# nivel_digital.net
KiCad netlist of a schematic drawn in EAGLE
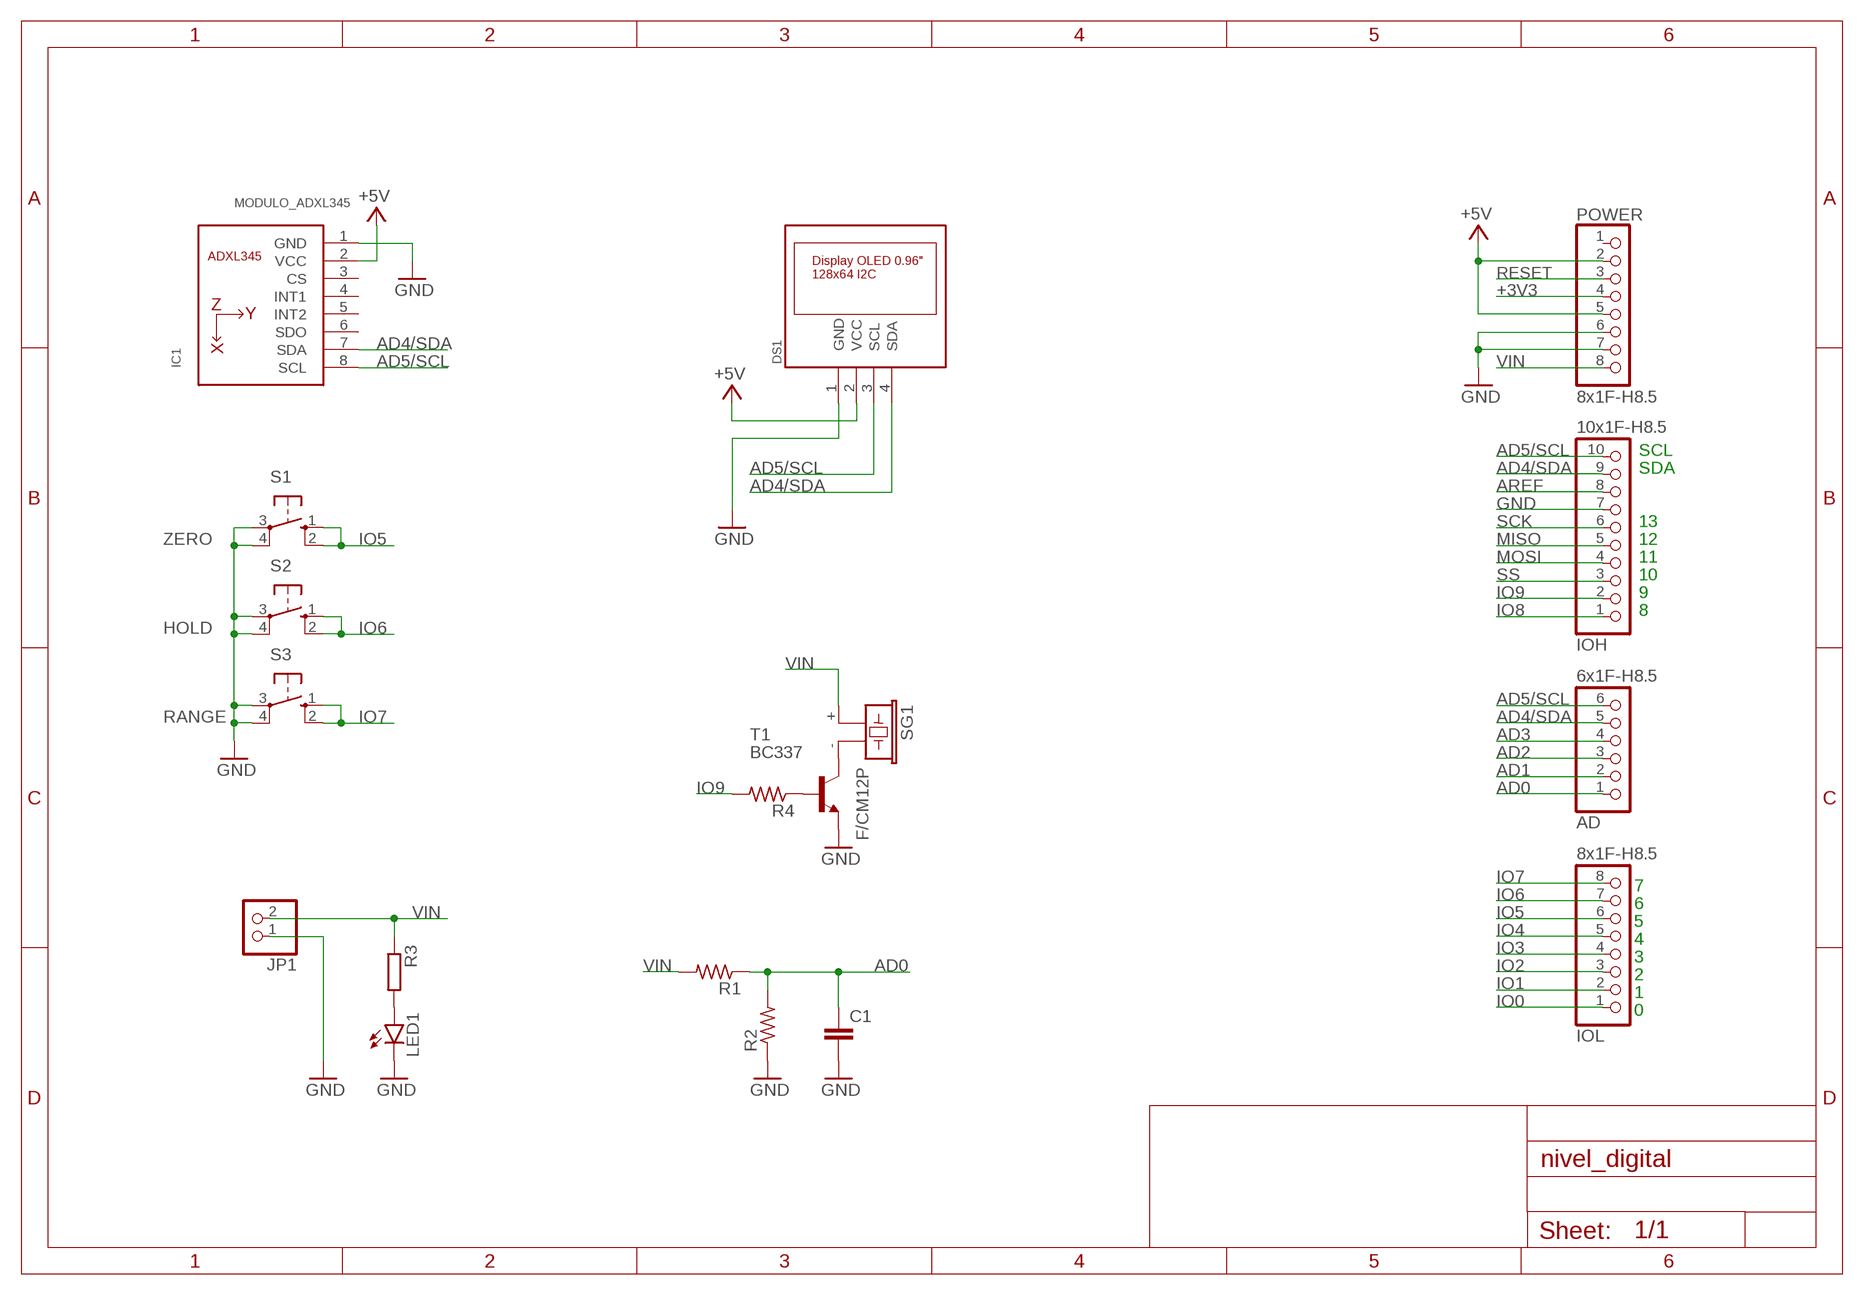
[diagram p0: schematic, sheet 1]

(export (version "E")
  (design (tool "Eeschema 10.0.6"))
  (components
    (comp (ref "AD")
      (value "6x1F-H8.5")
      (footprint "eagle-import:1X06")
      (libsource (lib "eagle-import") (part "PINHD-1X6"))
    )
    (comp (ref "C1")
      (value "C-EU050-025X075")
      (footprint "eagle-import:C050-025X075")
      (libsource (lib "eagle-import") (part "C-EU050-025X075"))
    )
    (comp (ref "DS1")
      (value "OLED_0.96_I2C")
      (footprint "eagle-import:OLED_0.96_I2C")
      (libsource (lib "eagle-import") (part "OLED_0.96_I2C"))
    )
    (comp (ref "IC1")
      (value "MODULO_ADXL345")
      (footprint "eagle-import:MODULO_ADXL345")
      (libsource (lib "eagle-import") (part "MODULO_ADXL345"))
    )
    (comp (ref "IOH")
      (value "10x1F-H8.5")
      (footprint "eagle-import:1X10")
      (libsource (lib "eagle-import") (part "PINHD-1X10_ARD"))
    )
    (comp (ref "IOL")
      (value "8x1F-H8.5")
      (footprint "eagle-import:1X08")
      (libsource (lib "eagle-import") (part "PINHD-1X8"))
    )
    (comp (ref "JP1")
      (value "PINHD-1X2/90")
      (footprint "eagle-import:1X02_90")
      (libsource (lib "eagle-import") (part "PINHD-1X2/90"))
    )
    (comp (ref "LED1")
      (value "LED5MM")
      (footprint "eagle-import:LED5MM")
      (libsource (lib "eagle-import") (part "LED5MM"))
    )
    (comp (ref "POWER")
      (value "8x1F-H8.5")
      (footprint "eagle-import:1X08")
      (libsource (lib "eagle-import") (part "PINHD-1X8"))
    )
    (comp (ref "R1")
      (value "R-US_0204/7")
      (footprint "eagle-import:0204_7")
      (libsource (lib "eagle-import") (part "R-US_0204/7"))
    )
    (comp (ref "R2")
      (value "R-US_0204/7")
      (footprint "eagle-import:0204_7")
      (libsource (lib "eagle-import") (part "R-US_0204/7"))
    )
    (comp (ref "R3")
      (value "R-EU_0207/10")
      (footprint "eagle-import:0207_10")
      (libsource (lib "eagle-import") (part "R-EU_0207/10"))
    )
    (comp (ref "R4")
      (value "R-US_0204/7")
      (footprint "eagle-import:0204_7")
      (libsource (lib "eagle-import") (part "R-US_0204/7"))
    )
    (comp (ref "S1")
      (value "10-XXPUSH-BUTTON-5MM")
      (footprint "eagle-import:B3F-10XX")
      (libsource (lib "eagle-import") (part "10-XXPUSH-BUTTON-5MM"))
    )
    (comp (ref "S2")
      (value "10-XXPUSH-BUTTON-5MM")
      (footprint "eagle-import:B3F-10XX")
      (libsource (lib "eagle-import") (part "10-XXPUSH-BUTTON-5MM"))
    )
    (comp (ref "S3")
      (value "10-XXPUSH-BUTTON-5MM")
      (footprint "eagle-import:B3F-10XX")
      (libsource (lib "eagle-import") (part "10-XXPUSH-BUTTON-5MM"))
    )
    (comp (ref "SG1")
      (value "F/CM12P")
      (footprint "eagle-import:F_CM12P")
      (libsource (lib "eagle-import") (part "F/CM12P"))
    )
    (comp (ref "T1")
      (value "BC337")
      (footprint "eagle-import:TO92")
      (libsource (lib "eagle-import") (part "BC337"))
    )
  )
  (nets
    (net (code "1") (name "+5V") (class "Default")
      (node (ref "DS1") (pin "2") (pinfunction "VCC_2") (pintype "power_in"))
      (node (ref "IC1") (pin "2") (pinfunction "VCC_2") (pintype "power_in"))
      (node (ref "POWER") (pin "2") (pinfunction "2_2") (pintype "passive"))
      (node (ref "POWER") (pin "5") (pinfunction "5_5") (pintype "passive"))
    )
    (net (code "2") (name "/+3V3") (class "Default")
      (node (ref "POWER") (pin "4") (pinfunction "4_4") (pintype "passive"))
    )
    (net (code "3") (name "/AD0") (class "Default")
      (node (ref "AD") (pin "1") (pinfunction "1_1") (pintype "passive"))
      (node (ref "C1") (pin "1") (pinfunction "1_1") (pintype "passive"))
      (node (ref "R1") (pin "1") (pinfunction "1_1") (pintype "passive"))
      (node (ref "R2") (pin "2") (pinfunction "2_2") (pintype "passive"))
    )
    (net (code "4") (name "/AD1") (class "Default")
      (node (ref "AD") (pin "2") (pinfunction "2_2") (pintype "passive"))
    )
    (net (code "5") (name "/AD2") (class "Default")
      (node (ref "AD") (pin "3") (pinfunction "3_3") (pintype "passive"))
    )
    (net (code "6") (name "/AD3") (class "Default")
      (node (ref "AD") (pin "4") (pinfunction "4_4") (pintype "passive"))
    )
    (net (code "7") (name "/AD4{slash}SDA") (class "Default")
      (node (ref "AD") (pin "5") (pinfunction "5_5") (pintype "passive"))
      (node (ref "DS1") (pin "4") (pinfunction "SDA_4") (pintype "bidirectional"))
      (node (ref "IC1") (pin "7") (pinfunction "SDA_7") (pintype "bidirectional"))
      (node (ref "IOH") (pin "9") (pinfunction "9_9") (pintype "passive"))
    )
    (net (code "8") (name "/AD5{slash}SCL") (class "Default")
      (node (ref "AD") (pin "6") (pinfunction "6_6") (pintype "passive"))
      (node (ref "DS1") (pin "3") (pinfunction "SCL_3") (pintype "bidirectional"))
      (node (ref "IC1") (pin "8") (pinfunction "SCL_8") (pintype "input"))
      (node (ref "IOH") (pin "10") (pinfunction "10_10") (pintype "passive"))
    )
    (net (code "9") (name "/AREF") (class "Default")
      (node (ref "IOH") (pin "8") (pinfunction "8_8") (pintype "passive"))
    )
    (net (code "10") (name "/IO0") (class "Default")
      (node (ref "IOL") (pin "1") (pinfunction "1_1") (pintype "passive"))
    )
    (net (code "11") (name "/IO1") (class "Default")
      (node (ref "IOL") (pin "2") (pinfunction "2_2") (pintype "passive"))
    )
    (net (code "12") (name "/IO2") (class "Default")
      (node (ref "IOL") (pin "3") (pinfunction "3_3") (pintype "passive"))
    )
    (net (code "13") (name "/IO3") (class "Default")
      (node (ref "IOL") (pin "4") (pinfunction "4_4") (pintype "passive"))
    )
    (net (code "14") (name "/IO4") (class "Default")
      (node (ref "IOL") (pin "5") (pinfunction "5_5") (pintype "passive"))
    )
    (net (code "15") (name "/IO5") (class "Default")
      (node (ref "IOL") (pin "6") (pinfunction "6_6") (pintype "passive"))
      (node (ref "S1") (pin "1") (pinfunction "S_1") (pintype "passive"))
      (node (ref "S1") (pin "2") (pinfunction "S1_2") (pintype "passive"))
    )
    (net (code "16") (name "/IO6") (class "Default")
      (node (ref "IOL") (pin "7") (pinfunction "7_7") (pintype "passive"))
      (node (ref "S2") (pin "1") (pinfunction "S_1") (pintype "passive"))
      (node (ref "S2") (pin "2") (pinfunction "S1_2") (pintype "passive"))
    )
    (net (code "17") (name "/IO7") (class "Default")
      (node (ref "IOL") (pin "8") (pinfunction "8_8") (pintype "passive"))
      (node (ref "S3") (pin "1") (pinfunction "S_1") (pintype "passive"))
      (node (ref "S3") (pin "2") (pinfunction "S1_2") (pintype "passive"))
    )
    (net (code "18") (name "/IO8") (class "Default")
      (node (ref "IOH") (pin "1") (pinfunction "1_1") (pintype "passive"))
    )
    (net (code "19") (name "/IO9") (class "Default")
      (node (ref "IOH") (pin "2") (pinfunction "2_2") (pintype "passive"))
      (node (ref "R4") (pin "2") (pinfunction "2_2") (pintype "passive"))
    )
    (net (code "20") (name "/MISO") (class "Default")
      (node (ref "IOH") (pin "5") (pinfunction "5_5") (pintype "passive"))
    )
    (net (code "21") (name "/MOSI") (class "Default")
      (node (ref "IOH") (pin "4") (pinfunction "4_4") (pintype "passive"))
    )
    (net (code "22") (name "/RESET") (class "Default")
      (node (ref "POWER") (pin "3") (pinfunction "3_3") (pintype "passive"))
    )
    (net (code "23") (name "/SCK") (class "Default")
      (node (ref "IOH") (pin "6") (pinfunction "6_6") (pintype "passive"))
    )
    (net (code "24") (name "/SS") (class "Default")
      (node (ref "IOH") (pin "3") (pinfunction "3_3") (pintype "passive"))
    )
    (net (code "25") (name "/VIN") (class "Default")
      (node (ref "JP1") (pin "2") (pinfunction "2_2") (pintype "passive"))
      (node (ref "POWER") (pin "8") (pinfunction "8_8") (pintype "passive"))
      (node (ref "R1") (pin "2") (pinfunction "2_2") (pintype "passive"))
      (node (ref "R3") (pin "1") (pinfunction "1_1") (pintype "passive"))
      (node (ref "SG1") (pin "+") (pinfunction "1_+") (pintype "passive"))
    )
    (net (code "26") (name "GND") (class "Default")
      (node (ref "C1") (pin "2") (pinfunction "2_2") (pintype "passive"))
      (node (ref "DS1") (pin "1") (pinfunction "GND_1") (pintype "power_in"))
      (node (ref "IC1") (pin "1") (pinfunction "GND_1") (pintype "power_in"))
      (node (ref "IOH") (pin "7") (pinfunction "7_7") (pintype "passive"))
      (node (ref "JP1") (pin "1") (pinfunction "1_1") (pintype "passive"))
      (node (ref "LED1") (pin "K") (pinfunction "C_K") (pintype "passive"))
      (node (ref "POWER") (pin "6") (pinfunction "6_6") (pintype "passive"))
      (node (ref "POWER") (pin "7") (pinfunction "7_7") (pintype "passive"))
      (node (ref "R2") (pin "1") (pinfunction "1_1") (pintype "passive"))
      (node (ref "S1") (pin "3") (pinfunction "P_3") (pintype "passive"))
      (node (ref "S1") (pin "4") (pinfunction "P1_4") (pintype "passive"))
      (node (ref "S2") (pin "3") (pinfunction "P_3") (pintype "passive"))
      (node (ref "S2") (pin "4") (pinfunction "P1_4") (pintype "passive"))
      (node (ref "S3") (pin "3") (pinfunction "P_3") (pintype "passive"))
      (node (ref "S3") (pin "4") (pinfunction "P1_4") (pintype "passive"))
      (node (ref "T1") (pin "1") (pinfunction "E_1") (pintype "passive"))
    )
    (net (code "27") (name "Net-(LED1-PadA)") (class "Default")
      (node (ref "LED1") (pin "A") (pinfunction "A_A") (pintype "passive"))
      (node (ref "R3") (pin "2") (pinfunction "2_2") (pintype "passive"))
    )
    (net (code "28") (name "Net-(SG1-2)") (class "Default")
      (node (ref "SG1") (pin "-") (pinfunction "2_-") (pintype "passive"))
      (node (ref "T1") (pin "3") (pinfunction "C_3") (pintype "passive"))
    )
    (net (code "29") (name "Net-(T1-B)") (class "Default")
      (node (ref "R4") (pin "1") (pinfunction "1_1") (pintype "passive"))
      (node (ref "T1") (pin "2") (pinfunction "B_2") (pintype "passive"))
    )
    (net (code "30") (name "unconnected-(IC1-CS-Pad3)") (class "Default")
      (node (ref "IC1") (pin "3") (pinfunction "CS_3") (pintype "input"))
    )
    (net (code "31") (name "unconnected-(IC1-INT1-Pad4)") (class "Default")
      (node (ref "IC1") (pin "4") (pinfunction "INT1_4") (pintype "output"))
    )
    (net (code "32") (name "unconnected-(IC1-INT2-Pad5)") (class "Default")
      (node (ref "IC1") (pin "5") (pinfunction "INT2_5") (pintype "output"))
    )
    (net (code "33") (name "unconnected-(IC1-SDO-Pad6)") (class "Default")
      (node (ref "IC1") (pin "6") (pinfunction "SDO_6") (pintype "bidirectional"))
    )
    (net (code "34") (name "unconnected-(POWER-Pad1)") (class "Default")
      (node (ref "POWER") (pin "1") (pinfunction "1_1") (pintype "passive"))
    )
  )
)
